# power.net
KiCad netlist of a schematic drawn in Altium Designer
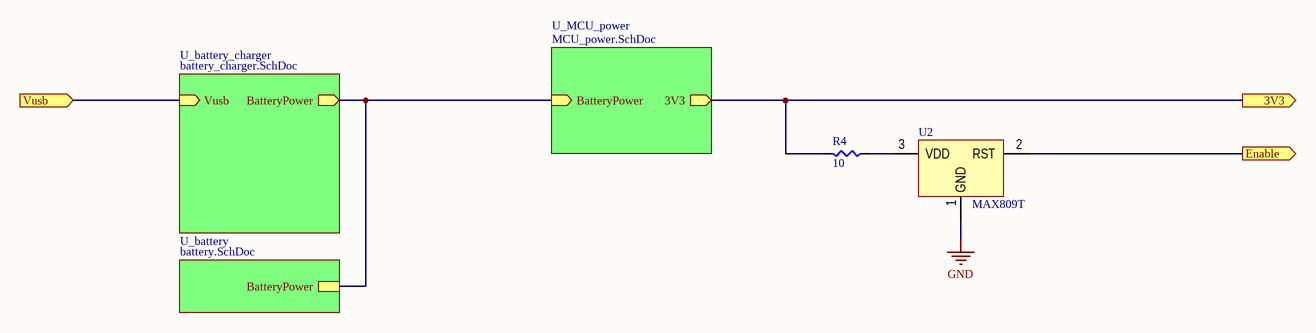
[diagram p0: power.SchDoc]

(export (version "E")
  (design (tool "Eeschema 10.0.6"))
  (components
    (comp (ref "R4")
      (value "10")
      (footprint "RES0603")
      (description "Tolerance ±1%\nPower (Watts) 0.1W, 1/10W\nTemperature Coefficient ±100ppm/°C")
      (fields (field (name "PART NUMBER") "RC0603FR-0710RL") (field (name "TOLERANCE") "1%"))
      (libsource (lib "Lib_Kam") (part "Resistor"))
    )
    (comp (ref "U2")
      (value "MAX809T")
      (footprint "SOT-23-3")
      (description "Power monitor 3.08В SOT23-3")
      (fields (field (name "MANUFACTURER") "UMW"))
      (libsource (lib "Lib_Kam") (part "MAX809"))
    )
  )
  (nets
    (net (code "1") (name "/3V3") (class "Default") (node (ref "R4") (pin "1") (pintype "passive")))
    (net (code "3") (name "/Enable") (class "Default")
      (node (ref "U2") (pin "2") (pinfunction "RST_2") (pintype "passive"))
    )
    (net (code "5") (name "GND") (class "Default")
      (node (ref "U2") (pin "1") (pinfunction "GND_1") (pintype "passive"))
    )
    (net (code "6") (name "Net-(U2-VDD)") (class "Default")
      (node (ref "R4") (pin "2") (pintype "passive"))
      (node (ref "U2") (pin "3") (pinfunction "VDD_3") (pintype "passive"))
    )
  )
)
